# SCH_555-LED-Decor_2025-11-10.net
KiCad netlist of a schematic drawn in EasyEDA
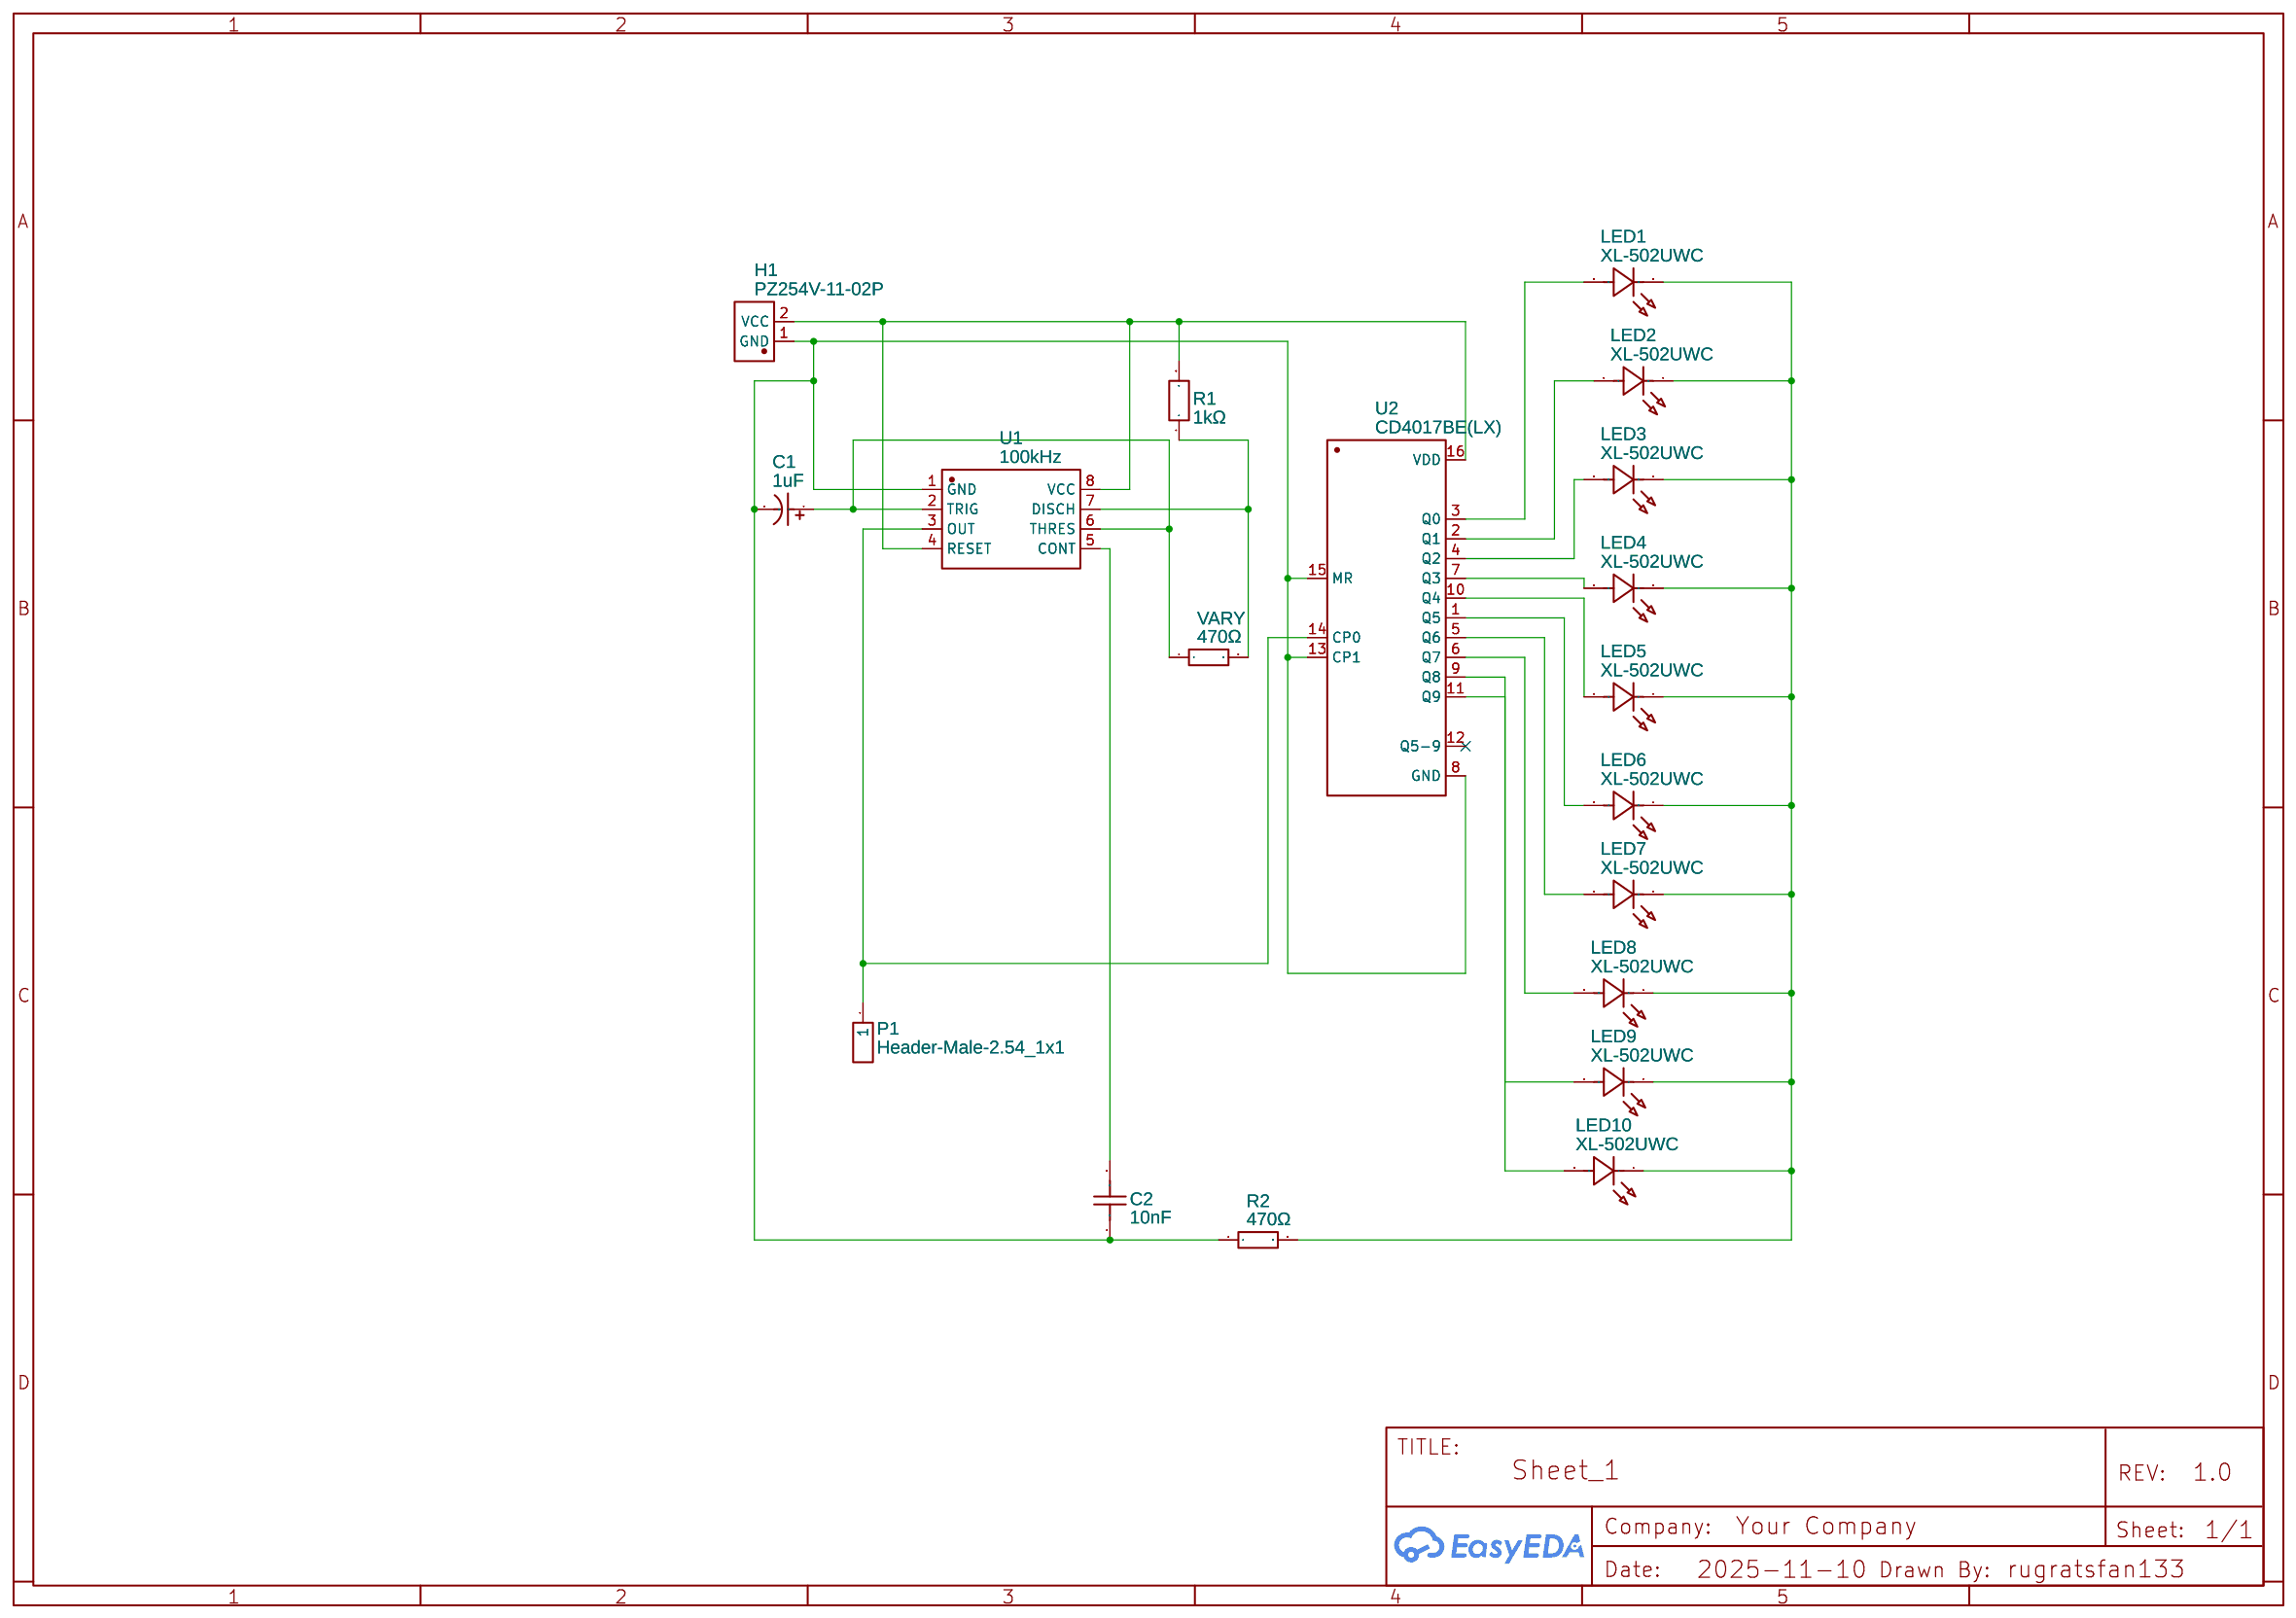
[diagram p0: schematic sheet]

(export (version "E")
  (design (tool "Eeschema 10.0.6"))
  (components
    (comp (ref "C1")
      (value "1uF")
      (fields (field (name "Manufacturer Part") "KF010M050C110A") (field (name "Manufacturer") "CapXon(丰宾)"))
      (libsource (lib "") (part "KF010M050C110A"))
    )
    (comp (ref "C2")
      (value "10nF")
      (fields (field (name "Manufacturer Part") "N09F1B103MN0B0S0N0") (field (name "Manufacturer") "STE(松田)"))
      (libsource (lib "") (part "N09F1B103MN0B0S0N0"))
    )
    (comp (ref "H1")
      (value "PZ254V-11-02P")
      (fields (field (name "Manufacturer") "XFCN(兴飞)"))
      (libsource (lib "") (part "PZ254V-11-02P"))
    )
    (comp (ref "LED1")
      (value "XL-502UWC")
      (fields (field (name "Manufacturer") "XINGLIGHT(成兴光)"))
      (libsource (lib "") (part "XL-502UWC"))
    )
    (comp (ref "LED2")
      (value "XL-502UWC")
      (fields (field (name "Manufacturer") "XINGLIGHT(成兴光)"))
      (libsource (lib "") (part "XL-502UWC"))
    )
    (comp (ref "LED3")
      (value "XL-502UWC")
      (fields (field (name "Manufacturer") "XINGLIGHT(成兴光)"))
      (libsource (lib "") (part "XL-502UWC"))
    )
    (comp (ref "LED4")
      (value "XL-502UWC")
      (fields (field (name "Manufacturer") "XINGLIGHT(成兴光)"))
      (libsource (lib "") (part "XL-502UWC"))
    )
    (comp (ref "LED5")
      (value "XL-502UWC")
      (fields (field (name "Manufacturer") "XINGLIGHT(成兴光)"))
      (libsource (lib "") (part "XL-502UWC"))
    )
    (comp (ref "LED6")
      (value "XL-502UWC")
      (fields (field (name "Manufacturer") "XINGLIGHT(成兴光)"))
      (libsource (lib "") (part "XL-502UWC"))
    )
    (comp (ref "LED7")
      (value "XL-502UWC")
      (fields (field (name "Manufacturer") "XINGLIGHT(成兴光)"))
      (libsource (lib "") (part "XL-502UWC"))
    )
    (comp (ref "LED8")
      (value "XL-502UWC")
      (fields (field (name "Manufacturer") "XINGLIGHT(成兴光)"))
      (libsource (lib "") (part "XL-502UWC"))
    )
    (comp (ref "LED9")
      (value "XL-502UWC")
      (fields (field (name "Manufacturer") "XINGLIGHT(成兴光)"))
      (libsource (lib "") (part "XL-502UWC"))
    )
    (comp (ref "LED10")
      (value "XL-502UWC")
      (fields (field (name "Manufacturer") "XINGLIGHT(成兴光)"))
      (libsource (lib "") (part "XL-502UWC"))
    )
    (comp (ref "P1")
      (value "Header-Male-2.54_1x1")
      (fields (field (name "Manufacturer Part") "2.54-1*1P针") (field (name "Manufacturer") "BOOMELE(博穆精密)"))
      (libsource (lib "") (part "Header-Male-2.54_1x1"))
    )
    (comp (ref "R1")
      (value "1kΩ")
      (fields (field (name "Manufacturer Part") "MF1/4W-1KΩ±1%T52") (field (name "Manufacturer") "华星机电"))
      (libsource (lib "") (part "MF1/4W-1KΩ±1%T52"))
    )
    (comp (ref "R2")
      (value "470Ω")
      (fields
        (field (name "Manufacturer Part") "MFR0W4F4700A50")
        (field (name "Manufacturer") "UNI-ROYAL(厚声)")
      )
      (libsource (lib "") (part "MFR0W4F4700A50"))
    )
    (comp (ref "U1")
      (value "100kHz")
      (fields (field (name "Manufacturer Part") "NE555P") (field (name "Manufacturer") "TI(德州仪器)"))
      (libsource (lib "") (part "NE555P"))
    )
    (comp (ref "U2")
      (value "CD4017BE(LX)")
      (fields (field (name "Manufacturer") "LX(灵星芯微)"))
      (libsource (lib "") (part "CD4017BE(LX)"))
    )
    (comp (ref "VARY")
      (value "470Ω")
      (fields
        (field (name "Manufacturer Part") "MFR0W4F4700A50")
        (field (name "Manufacturer") "UNI-ROYAL(厚声)")
      )
      (libsource (lib "") (part "MFR0W4F4700A50_1"))
    )
  )
  (nets
    (net (code "1") (name "Net-(H1-GND)") (class "Default")
      (node (ref "C1") (pin "2") (pinfunction "2_2") (pintype "input"))
      (node (ref "C2") (pin "1") (pinfunction "1_1") (pintype "unspecified"))
      (node (ref "H1") (pin "1") (pinfunction "GND_1") (pintype "unspecified"))
      (node (ref "R2") (pin "1") (pinfunction "1_1") (pintype "input"))
      (node (ref "U1") (pin "1") (pinfunction "GND_1") (pintype "unspecified"))
      (node (ref "U2") (pin "13") (pinfunction "CP1_13") (pintype "unspecified"))
      (node (ref "U2") (pin "15") (pinfunction "MR_15") (pintype "unspecified"))
      (node (ref "U2") (pin "8") (pinfunction "GND_8") (pintype "unspecified"))
    )
    (net (code "2") (name "Net-(H1-VCC)") (class "Default")
      (node (ref "H1") (pin "2") (pinfunction "VCC_2") (pintype "unspecified"))
      (node (ref "R1") (pin "2") (pinfunction "2_2") (pintype "unspecified"))
      (node (ref "U1") (pin "4") (pinfunction "RESET_4") (pintype "unspecified"))
      (node (ref "U1") (pin "8") (pinfunction "VCC_8") (pintype "unspecified"))
      (node (ref "U2") (pin "16") (pinfunction "VDD_16") (pintype "unspecified"))
    )
    (net (code "3") (name "Net-(LED1-A)") (class "Default")
      (node (ref "LED1") (pin "2") (pinfunction "A_2") (pintype "unspecified"))
      (node (ref "U2") (pin "3") (pinfunction "Q0_3") (pintype "unspecified"))
    )
    (net (code "4") (name "Net-(LED1-K)") (class "Default")
      (node (ref "LED1") (pin "1") (pinfunction "K_1") (pintype "unspecified"))
      (node (ref "LED10") (pin "1") (pinfunction "K_1") (pintype "unspecified"))
      (node (ref "LED2") (pin "1") (pinfunction "K_1") (pintype "unspecified"))
      (node (ref "LED3") (pin "1") (pinfunction "K_1") (pintype "unspecified"))
      (node (ref "LED4") (pin "1") (pinfunction "K_1") (pintype "unspecified"))
      (node (ref "LED5") (pin "1") (pinfunction "K_1") (pintype "unspecified"))
      (node (ref "LED6") (pin "1") (pinfunction "K_1") (pintype "unspecified"))
      (node (ref "LED7") (pin "1") (pinfunction "K_1") (pintype "unspecified"))
      (node (ref "LED8") (pin "1") (pinfunction "K_1") (pintype "unspecified"))
      (node (ref "LED9") (pin "1") (pinfunction "K_1") (pintype "unspecified"))
      (node (ref "R2") (pin "2") (pinfunction "2_2") (pintype "input"))
    )
    (net (code "5") (name "Net-(LED2-A)") (class "Default")
      (node (ref "LED2") (pin "2") (pinfunction "A_2") (pintype "unspecified"))
      (node (ref "U2") (pin "2") (pinfunction "Q1_2") (pintype "unspecified"))
    )
    (net (code "6") (name "Net-(LED3-A)") (class "Default")
      (node (ref "LED3") (pin "2") (pinfunction "A_2") (pintype "unspecified"))
      (node (ref "U2") (pin "4") (pinfunction "Q2_4") (pintype "unspecified"))
    )
    (net (code "7") (name "Net-(LED4-A)") (class "Default")
      (node (ref "LED4") (pin "2") (pinfunction "A_2") (pintype "unspecified"))
      (node (ref "U2") (pin "7") (pinfunction "Q3_7") (pintype "unspecified"))
    )
    (net (code "8") (name "Net-(LED5-A)") (class "Default")
      (node (ref "LED5") (pin "2") (pinfunction "A_2") (pintype "unspecified"))
      (node (ref "U2") (pin "10") (pinfunction "Q4_10") (pintype "unspecified"))
    )
    (net (code "9") (name "Net-(LED6-A)") (class "Default")
      (node (ref "LED6") (pin "2") (pinfunction "A_2") (pintype "unspecified"))
      (node (ref "U2") (pin "1") (pinfunction "Q5_1") (pintype "unspecified"))
    )
    (net (code "10") (name "Net-(LED7-A)") (class "Default")
      (node (ref "LED7") (pin "2") (pinfunction "A_2") (pintype "unspecified"))
      (node (ref "U2") (pin "5") (pinfunction "Q6_5") (pintype "unspecified"))
    )
    (net (code "11") (name "Net-(LED8-A)") (class "Default")
      (node (ref "LED8") (pin "2") (pinfunction "A_2") (pintype "unspecified"))
      (node (ref "U2") (pin "6") (pinfunction "Q7_6") (pintype "unspecified"))
    )
    (net (code "12") (name "Net-(LED9-A)") (class "Default")
      (node (ref "LED9") (pin "2") (pinfunction "A_2") (pintype "unspecified"))
      (node (ref "U2") (pin "9") (pinfunction "Q8_9") (pintype "unspecified"))
    )
    (net (code "13") (name "Net-(LED10-A)") (class "Default")
      (node (ref "LED10") (pin "2") (pinfunction "A_2") (pintype "unspecified"))
      (node (ref "U2") (pin "11") (pinfunction "Q9_11") (pintype "unspecified"))
    )
    (net (code "14") (name "Net-(U1-CONT)") (class "Default")
      (node (ref "C2") (pin "2") (pinfunction "2_2") (pintype "unspecified"))
      (node (ref "U1") (pin "5") (pinfunction "CONT_5") (pintype "unspecified"))
    )
    (net (code "15") (name "Net-(U1-DISCH)") (class "Default")
      (node (ref "R1") (pin "1") (pinfunction "1_1") (pintype "unspecified"))
      (node (ref "U1") (pin "7") (pinfunction "DISCH_7") (pintype "unspecified"))
      (node (ref "VARY") (pin "2") (pinfunction "2_2") (pintype "input"))
    )
    (net (code "16") (name "Net-(U1-OUT)") (class "Default")
      (node (ref "P1") (pin "1") (pinfunction "1_1") (pintype "input"))
      (node (ref "U1") (pin "3") (pinfunction "OUT_3") (pintype "unspecified"))
      (node (ref "U2") (pin "14") (pinfunction "CP0_14") (pintype "unspecified"))
    )
    (net (code "17") (name "Net-(U1-THRES)") (class "Default")
      (node (ref "C1") (pin "1") (pinfunction "1_1") (pintype "input"))
      (node (ref "U1") (pin "2") (pinfunction "TRIG_2") (pintype "unspecified"))
      (node (ref "U1") (pin "6") (pinfunction "THRES_6") (pintype "unspecified"))
      (node (ref "VARY") (pin "1") (pinfunction "1_1") (pintype "input"))
    )
    (net (code "18") (name "unconnected-(U2-Q5-9-Pad12)") (class "Default")
      (node (ref "U2") (pin "12") (pinfunction "Q5-9_12") (pintype "unspecified+no_connect"))
    )
  )
)
